# working.net
KiCad netlist of a schematic drawn in EAGLE
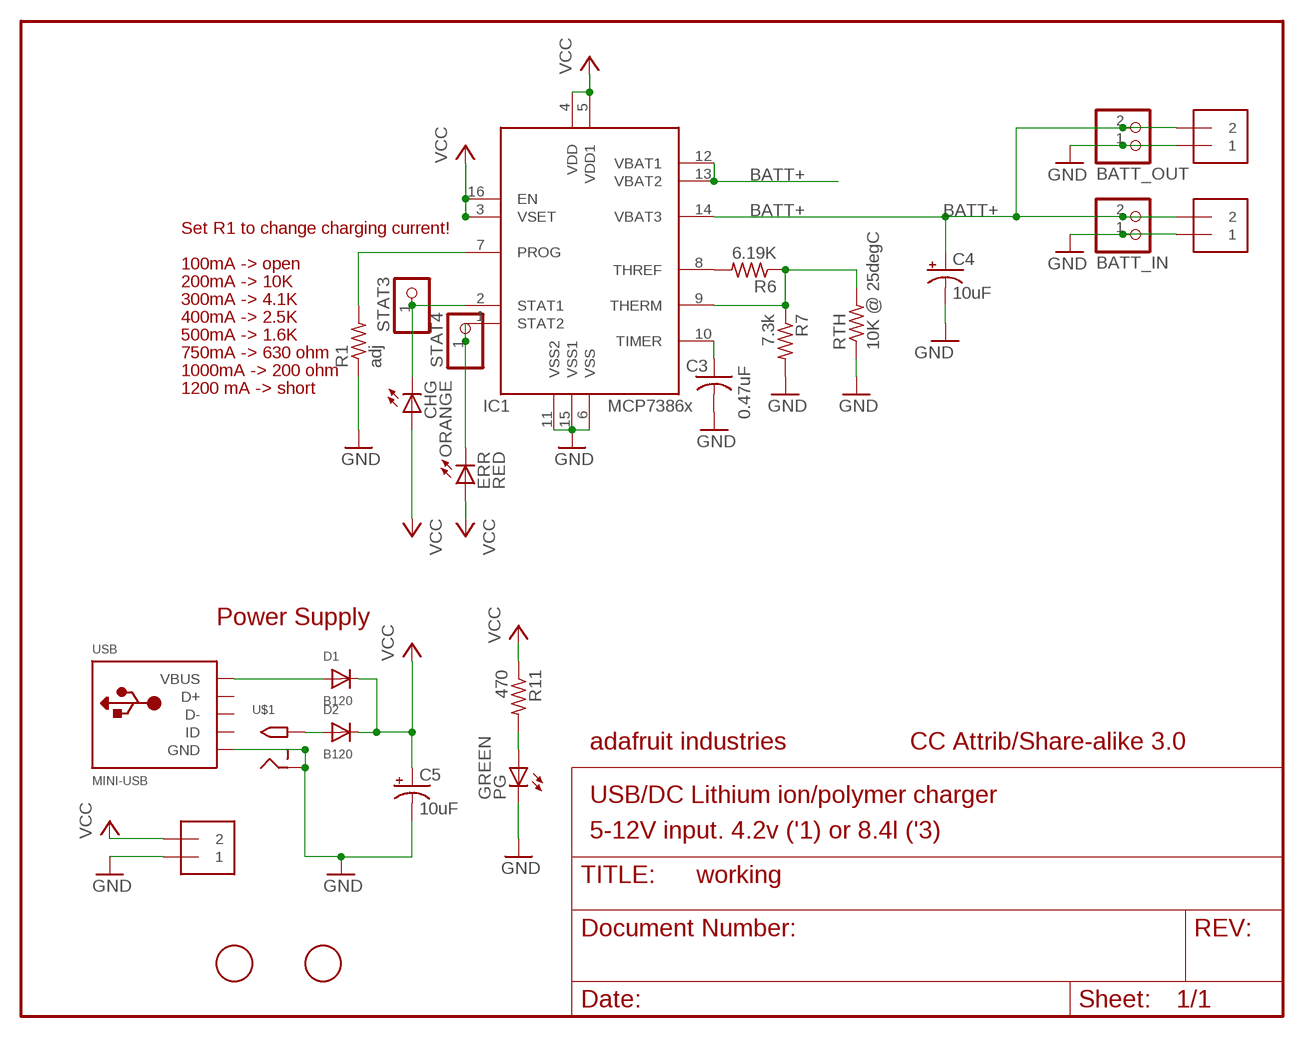
[diagram p0: schematic, sheet 1]

(export (version "E")
  (design (tool "Eeschema 10.0.6"))
  (components
    (comp (ref "BATT_IN")
      (value "JST_2PIN")
      (footprint "eagle-import:JSTPH2")
      (libsource (lib "eagle-import") (part "JST_2PIN"))
    )
    (comp (ref "BATT_OUT")
      (value "JST_2PIN")
      (footprint "eagle-import:JSTPH2")
      (libsource (lib "eagle-import") (part "JST_2PIN"))
    )
    (comp (ref "C3")
      (value "0.47uF")
      (footprint "eagle-import:C0805K")
      (libsource (lib "eagle-import") (part "C-USC0805K"))
    )
    (comp (ref "C4")
      (value "10uF")
      (footprint "eagle-import:A_3216-18R")
      (libsource (lib "eagle-import") (part "CPOL-USA/3216-18R"))
    )
    (comp (ref "C5")
      (value "10uF")
      (footprint "eagle-import:A_3216-18R")
      (libsource (lib "eagle-import") (part "CPOL-USA/3216-18R"))
    )
    (comp (ref "CHG")
      (value "ORANGE")
      (footprint "eagle-import:CHIPLED_0805")
      (libsource (lib "eagle-import") (part "LEDCHIPLED_0805"))
    )
    (comp (ref "D1")
      (value "B120")
      (footprint "eagle-import:SMADIODE")
      (libsource (lib "eagle-import") (part "DIODESMA"))
    )
    (comp (ref "D2")
      (value "B120")
      (footprint "eagle-import:SMADIODE")
      (libsource (lib "eagle-import") (part "DIODESMA"))
    )
    (comp (ref "ERR")
      (value "RED")
      (footprint "eagle-import:CHIPLED_0805")
      (libsource (lib "eagle-import") (part "LEDCHIPLED_0805"))
    )
    (comp (ref "IC1")
      (value "MCP7386XS")
      (footprint "eagle-import:SO16")
      (libsource (lib "eagle-import") (part "MCP7386XS"))
    )
    (comp (ref "IN")
      (value "1X2-3.5MM")
      (footprint "eagle-import:3.5MMTERM")
      (libsource (lib "eagle-import") (part "1X2-3.5MM"))
    )
    (comp (ref "OUT")
      (value "1X2-3.5MM")
      (footprint "eagle-import:3.5MMTERM")
      (libsource (lib "eagle-import") (part "1X2-3.5MM"))
    )
    (comp (ref "PG")
      (value "GREEN")
      (footprint "eagle-import:CHIPLED_0805")
      (libsource (lib "eagle-import") (part "LEDCHIPLED_0805"))
    )
    (comp (ref "R1")
      (value "adj")
      (footprint "eagle-import:0805-THM")
      (libsource (lib "eagle-import") (part "R-US_FLIPFLOP"))
    )
    (comp (ref "R6")
      (value "6.19K")
      (footprint "eagle-import:R0805")
      (libsource (lib "eagle-import") (part "R-US_R0805"))
    )
    (comp (ref "R7")
      (value "7.3k")
      (footprint "eagle-import:R0805")
      (libsource (lib "eagle-import") (part "R-US_R0805"))
    )
    (comp (ref "R11")
      (value "470")
      (footprint "eagle-import:R0805")
      (libsource (lib "eagle-import") (part "R-US_R0805"))
    )
    (comp (ref "RTH")
      (value "10K @ 25degC")
      (footprint "eagle-import:0805-THM")
      (libsource (lib "eagle-import") (part "R-US_FLIPFLOP"))
    )
    (comp (ref "STAT3")
      (value "PINHD-1X1")
      (footprint "eagle-import:1X01")
      (libsource (lib "eagle-import") (part "PINHD-1X1"))
    )
    (comp (ref "STAT4")
      (value "PINHD-1X1")
      (footprint "eagle-import:1X01")
      (libsource (lib "eagle-import") (part "PINHD-1X1"))
    )
    (comp (ref "U$1")
      (value "2.1MMJACKSMT")
      (footprint "eagle-import:DCJACK_2MM_SMT")
      (libsource (lib "eagle-import") (part "2.1MMJACKSMT"))
    )
    (comp (ref "U$3")
      (value "FIDUCIAL")
      (footprint "eagle-import:FIDUCIAL_1MM")
      (libsource (lib "eagle-import") (part "FIDUCIAL"))
    )
    (comp (ref "U$4")
      (value "FIDUCIAL")
      (footprint "eagle-import:FIDUCIAL_1MM")
      (libsource (lib "eagle-import") (part "FIDUCIAL"))
    )
    (comp (ref "USB")
      (value "MINI-USB")
      (footprint "eagle-import:USB-MINIB")
      (libsource (lib "eagle-import") (part "USBMINIB"))
    )
    (comp (ref "VIN")
      (value "1X2-3.5MM")
      (footprint "eagle-import:3.5MMTERM")
      (libsource (lib "eagle-import") (part "1X2-3.5MM"))
    )
  )
  (nets
    (net (code "1") (name "/BATT+") (class "Default")
      (node (ref "BATT_IN") (pin "2") (pinfunction "2_2") (pintype "passive"))
      (node (ref "BATT_OUT") (pin "2") (pinfunction "2_2") (pintype "passive"))
      (node (ref "C4") (pin "+") (pinfunction "+_+") (pintype "passive"))
      (node (ref "IC1") (pin "12") (pinfunction "VBAT1_12") (pintype "input"))
      (node (ref "IC1") (pin "13") (pinfunction "VBAT2_13") (pintype "input"))
      (node (ref "IC1") (pin "14") (pinfunction "VBAT3_14") (pintype "input"))
      (node (ref "IN") (pin "2") (pinfunction "2_2") (pintype "passive"))
      (node (ref "OUT") (pin "2") (pinfunction "2_2") (pintype "passive"))
    )
    (net (code "2") (name "GND") (class "Default")
      (node (ref "BATT_IN") (pin "1") (pinfunction "1_1") (pintype "passive"))
      (node (ref "BATT_OUT") (pin "1") (pinfunction "1_1") (pintype "passive"))
      (node (ref "C3") (pin "2") (pinfunction "2_2") (pintype "passive"))
      (node (ref "C4") (pin "-") (pinfunction "-_-") (pintype "passive"))
      (node (ref "C5") (pin "-") (pinfunction "-_-") (pintype "passive"))
      (node (ref "IC1") (pin "11") (pinfunction "VSS2_11") (pintype "power_in"))
      (node (ref "IC1") (pin "15") (pinfunction "VSS1_15") (pintype "power_in"))
      (node (ref "IC1") (pin "6") (pinfunction "VSS_6") (pintype "power_in"))
      (node (ref "IN") (pin "1") (pinfunction "1_1") (pintype "passive"))
      (node (ref "OUT") (pin "1") (pinfunction "1_1") (pintype "passive"))
      (node (ref "PG") (pin "C") (pinfunction "C_C") (pintype "passive"))
      (node (ref "R1") (pin "1") (pinfunction "1_1") (pintype "passive"))
      (node (ref "R7") (pin "2") (pinfunction "2_2") (pintype "passive"))
      (node (ref "RTH") (pin "1") (pinfunction "1_1") (pintype "passive"))
      (node (ref "U$1") (pin "GND") (pinfunction "RING_GND") (pintype "bidirectional"))
      (node (ref "U$1") (pin "GNDBREAK") (pinfunction "RING_SW_GNDBREAK") (pintype "bidirectional"))
      (node (ref "USB") (pin "GND") (pinfunction "GND_GND") (pintype "power_in"))
      (node (ref "VIN") (pin "1") (pinfunction "1_1") (pintype "passive"))
    )
    (net (code "3") (name "Net-(D1-PadA)") (class "Default")
      (node (ref "D1") (pin "A") (pinfunction "A_A") (pintype "passive"))
      (node (ref "USB") (pin "VBUS") (pinfunction "VBUS_VBUS") (pintype "power_in"))
    )
    (net (code "4") (name "Net-(IC1-PROG)") (class "Default")
      (node (ref "IC1") (pin "7") (pinfunction "PROG_7") (pintype "passive"))
      (node (ref "R1") (pin "2") (pinfunction "2_2") (pintype "passive"))
    )
    (net (code "5") (name "Net-(IC1-STAT1)") (class "Default")
      (node (ref "CHG") (pin "C") (pinfunction "C_C") (pintype "passive"))
      (node (ref "IC1") (pin "2") (pinfunction "STAT1_2") (pintype "output"))
      (node (ref "STAT3") (pin "1") (pinfunction "1_1") (pintype "passive"))
    )
    (net (code "6") (name "Net-(IC1-STAT2)") (class "Default")
      (node (ref "ERR") (pin "C") (pinfunction "C_C") (pintype "passive"))
      (node (ref "IC1") (pin "1") (pinfunction "STAT2_1") (pintype "output"))
      (node (ref "STAT4") (pin "1") (pinfunction "1_1") (pintype "passive"))
    )
    (net (code "7") (name "Net-(IC1-THERM)") (class "Default")
      (node (ref "IC1") (pin "9") (pinfunction "THERM_9") (pintype "passive"))
      (node (ref "R6") (pin "1") (pinfunction "1_1") (pintype "passive"))
      (node (ref "R7") (pin "1") (pinfunction "1_1") (pintype "passive"))
      (node (ref "RTH") (pin "2") (pinfunction "2_2") (pintype "passive"))
    )
    (net (code "8") (name "Net-(IC1-THREF)") (class "Default")
      (node (ref "IC1") (pin "8") (pinfunction "THREF_8") (pintype "passive"))
      (node (ref "R6") (pin "2") (pinfunction "2_2") (pintype "passive"))
    )
    (net (code "9") (name "Net-(IC1-TIMER)") (class "Default")
      (node (ref "C3") (pin "1") (pinfunction "1_1") (pintype "passive"))
      (node (ref "IC1") (pin "10") (pinfunction "TIMER_10") (pintype "passive"))
    )
    (net (code "10") (name "Net-(PG-PadA)") (class "Default")
      (node (ref "PG") (pin "A") (pinfunction "A_A") (pintype "passive"))
      (node (ref "R11") (pin "2") (pinfunction "2_2") (pintype "passive"))
    )
    (net (code "11") (name "Net-(U$1-TIP)") (class "Default")
      (node (ref "D2") (pin "A") (pinfunction "A_A") (pintype "passive"))
      (node (ref "U$1") (pin "PWR2") (pinfunction "TIP_PWR2") (pintype "bidirectional"))
    )
    (net (code "12") (name "VCC") (class "Default")
      (node (ref "C5") (pin "+") (pinfunction "+_+") (pintype "passive"))
      (node (ref "CHG") (pin "A") (pinfunction "A_A") (pintype "passive"))
      (node (ref "D1") (pin "C") (pinfunction "C_C") (pintype "passive"))
      (node (ref "D2") (pin "C") (pinfunction "C_C") (pintype "passive"))
      (node (ref "ERR") (pin "A") (pinfunction "A_A") (pintype "passive"))
      (node (ref "IC1") (pin "16") (pinfunction "EN_16") (pintype "input"))
      (node (ref "IC1") (pin "3") (pinfunction "VSET_3") (pintype "input"))
      (node (ref "IC1") (pin "4") (pinfunction "VDD_4") (pintype "power_in"))
      (node (ref "IC1") (pin "5") (pinfunction "VDD1_5") (pintype "power_in"))
      (node (ref "R11") (pin "1") (pinfunction "1_1") (pintype "passive"))
      (node (ref "VIN") (pin "2") (pinfunction "2_2") (pintype "passive"))
    )
    (net (code "13") (name "unconnected-(USB-PadD+)") (class "Default")
      (node (ref "USB") (pin "D+") (pinfunction "D+_D+") (pintype "bidirectional"))
    )
    (net (code "14") (name "unconnected-(USB-PadD-)") (class "Default")
      (node (ref "USB") (pin "D-") (pinfunction "D-_D-") (pintype "bidirectional"))
    )
    (net (code "15") (name "unconnected-(USB-PadID)") (class "Default")
      (node (ref "USB") (pin "ID") (pinfunction "ID_ID") (pintype "bidirectional"))
    )
  )
)
